# slipring.net
KiCad netlist of a schematic drawn in EAGLE
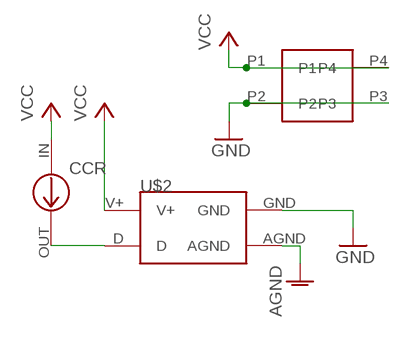
[diagram p0: schematic, sheet 1]

(export (version "E")
  (design (tool "Eeschema 10.0.6"))
  (components
    (comp (ref "CCR")
      (value "CCR")
      (footprint "eagle-import:CCR")
      (libsource (lib "eagle-import") (part "CCR"))
    )
    (comp (ref "CONN")
      (value "BOURNS_2PIN")
      (footprint "eagle-import:BOURNS_2PIN")
      (libsource (lib "eagle-import") (part "BOURNS_2PIN"))
    )
    (comp (ref "U$2")
      (value "RING3")
      (footprint "eagle-import:RING3")
      (libsource (lib "eagle-import") (part "RING3"))
    )
  )
  (nets
    (net (code "1") (name "AGND") (class "Default")
      (node (ref "U$2") (pin "AGND") (pinfunction "AGND_AGND") (pintype "bidirectional"))
    )
    (net (code "2") (name "GND") (class "Default")
      (node (ref "CONN") (pin "P2") (pinfunction "P2_P2") (pintype "bidirectional"))
      (node (ref "CONN") (pin "P3") (pinfunction "P3_P3") (pintype "bidirectional"))
      (node (ref "U$2") (pin "GND") (pinfunction "GND_GND") (pintype "bidirectional"))
    )
    (net (code "3") (name "Net-(CCR-PadOUT)") (class "Default")
      (node (ref "CCR") (pin "OUT") (pinfunction "OUT_OUT") (pintype "bidirectional"))
      (node (ref "U$2") (pin "D") (pinfunction "D_D") (pintype "bidirectional"))
    )
    (net (code "4") (name "VCC") (class "Default")
      (node (ref "CCR") (pin "IN") (pinfunction "IN_IN") (pintype "bidirectional"))
      (node (ref "CONN") (pin "P1") (pinfunction "P1_P1") (pintype "bidirectional"))
      (node (ref "CONN") (pin "P4") (pinfunction "P4_P4") (pintype "bidirectional"))
      (node (ref "U$2") (pin "V+") (pinfunction "V+_V+") (pintype "bidirectional"))
    )
  )
)
